# SCH_Front_Pulsadores.net
KiCad netlist of a schematic drawn in Altium Designer
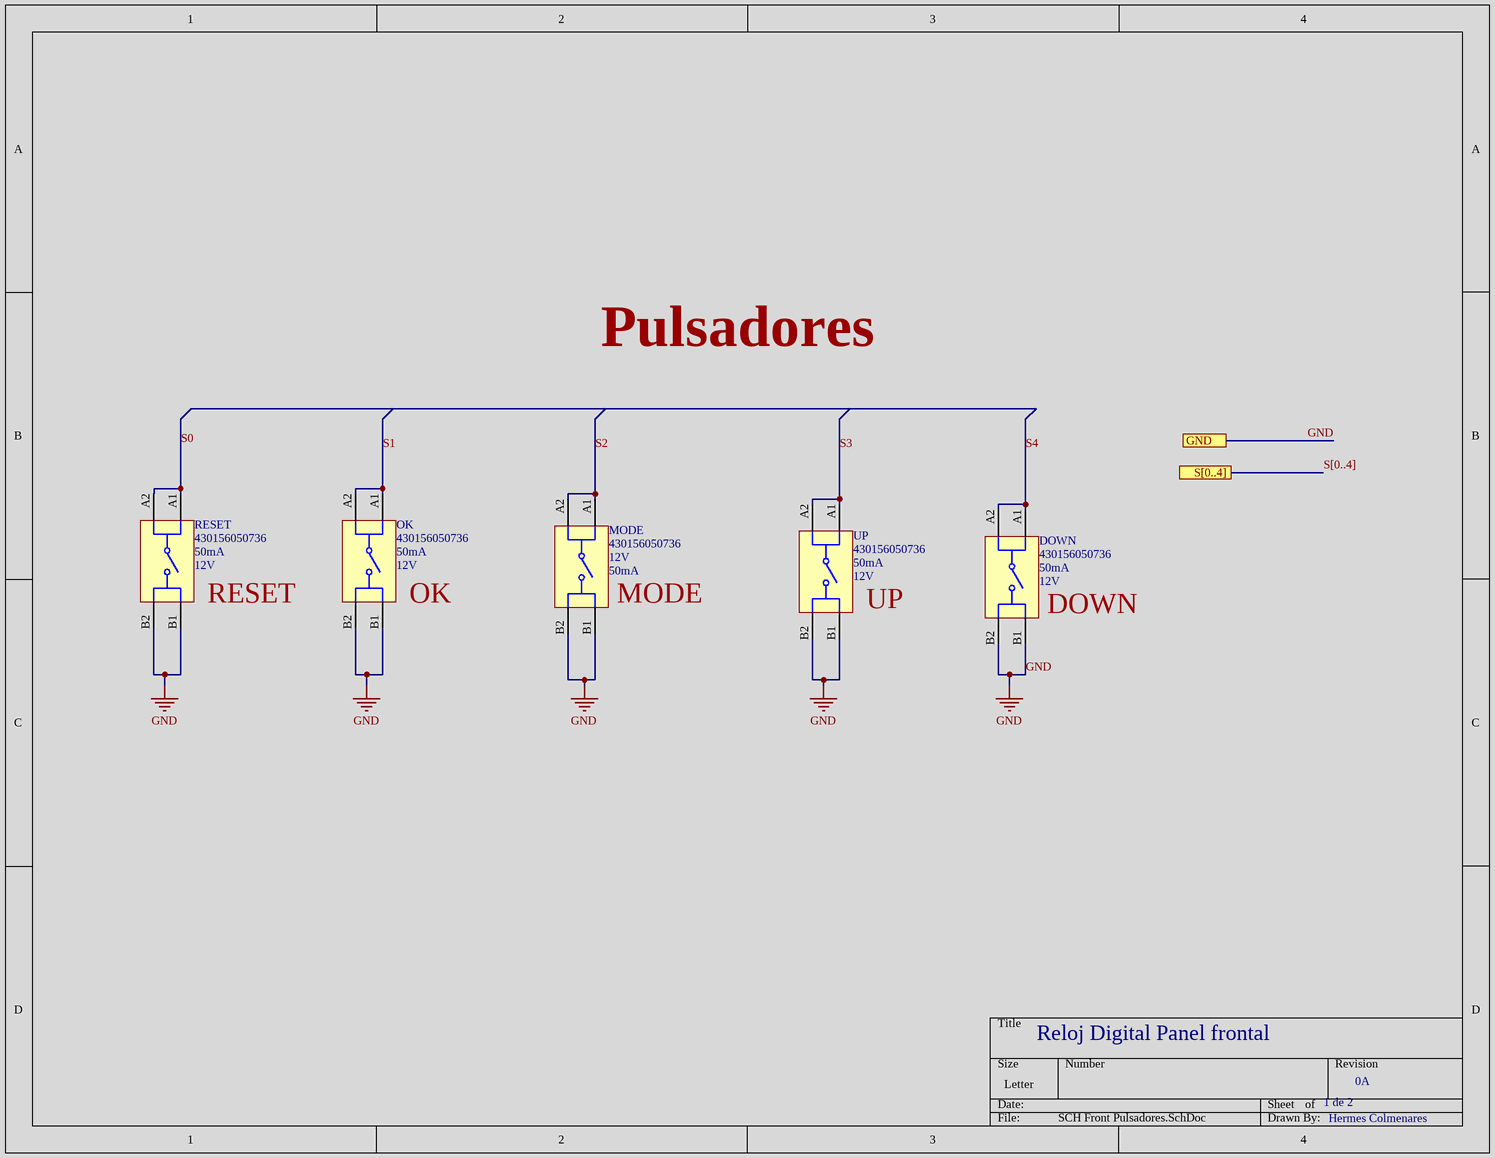
[diagram p0: SCH Front Pulsadores.SchDoc]

(export (version "E")
  (design (tool "Eeschema 10.0.6"))
  (components
    (comp (ref "DOWN")
      (value "430156050736")
      (footprint "4301x60507x6")
      (fields (field (name "CONTACT CURRENT RATING") "50mA") (field (name "VOLTAGE RATING") "12V"))
      (libsource (lib "Altium Content Vault") (part "SPST-NO_4P"))
    )
    (comp (ref "MODE")
      (value "430156050736")
      (footprint "4301x60507x6")
      (fields (field (name "VOLTAGE RATING") "12V") (field (name "CURRENT RATING") "50mA"))
      (libsource (lib "Altium Content Vault") (part "SPST-NO_4P"))
    )
    (comp (ref "OK")
      (value "430156050736")
      (footprint "4301x60507x6")
      (fields (field (name "CONTACT CURRENT RATING") "50mA") (field (name "VOLTAGE RATING") "12V"))
      (libsource (lib "Altium Content Vault") (part "SPST-NO_4P"))
    )
    (comp (ref "RESET")
      (value "430156050736")
      (footprint "4301x60507x6")
      (fields (field (name "CONTACT CURRENT RATING") "50mA") (field (name "VOLTAGE RATING") "12V"))
      (libsource (lib "Altium Content Vault") (part "SPST-NO_4P"))
    )
    (comp (ref "UP")
      (value "430156050736")
      (footprint "4301x60507x6")
      (fields (field (name "CONTACT CURRENT RATING") "50mA") (field (name "VOLTAGE RATING") "12V"))
      (libsource (lib "Altium Content Vault") (part "SPST-NO_4P"))
    )
  )
  (nets
    (net (code "1") (name "/S0") (class "Default")
      (node (ref "RESET") (pin "A1") (pinfunction "A1_A1") (pintype "passive"))
      (node (ref "RESET") (pin "A2") (pinfunction "A2_A2") (pintype "passive"))
    )
    (net (code "2") (name "/S1") (class "Default")
      (node (ref "OK") (pin "A1") (pinfunction "A1_A1") (pintype "passive"))
      (node (ref "OK") (pin "A2") (pinfunction "A2_A2") (pintype "passive"))
    )
    (net (code "3") (name "/S2") (class "Default")
      (node (ref "MODE") (pin "A1") (pinfunction "A1_A1") (pintype "passive"))
      (node (ref "MODE") (pin "A2") (pinfunction "A2_A2") (pintype "passive"))
    )
    (net (code "4") (name "/S3") (class "Default")
      (node (ref "UP") (pin "A1") (pinfunction "A1_A1") (pintype "passive"))
      (node (ref "UP") (pin "A2") (pinfunction "A2_A2") (pintype "passive"))
    )
    (net (code "5") (name "/S4") (class "Default")
      (node (ref "DOWN") (pin "A1") (pinfunction "A1_A1") (pintype "passive"))
      (node (ref "DOWN") (pin "A2") (pinfunction "A2_A2") (pintype "passive"))
    )
    (net (code "7") (name "GND") (class "Default")
      (node (ref "DOWN") (pin "B1") (pinfunction "B1_B1") (pintype "passive"))
      (node (ref "DOWN") (pin "B2") (pinfunction "B2_B2") (pintype "passive"))
      (node (ref "MODE") (pin "B1") (pinfunction "B1_B1") (pintype "passive"))
      (node (ref "MODE") (pin "B2") (pinfunction "B2_B2") (pintype "passive"))
      (node (ref "OK") (pin "B1") (pinfunction "B1_B1") (pintype "passive"))
      (node (ref "OK") (pin "B2") (pinfunction "B2_B2") (pintype "passive"))
      (node (ref "RESET") (pin "B1") (pinfunction "B1_B1") (pintype "passive"))
      (node (ref "RESET") (pin "B2") (pinfunction "B2_B2") (pintype "passive"))
      (node (ref "UP") (pin "B1") (pinfunction "B1_B1") (pintype "passive"))
      (node (ref "UP") (pin "B2") (pinfunction "B2_B2") (pintype "passive"))
    )
  )
)
